# mainboard_mcu_v1_6.net
KiCad netlist of a schematic drawn in Altium Designer
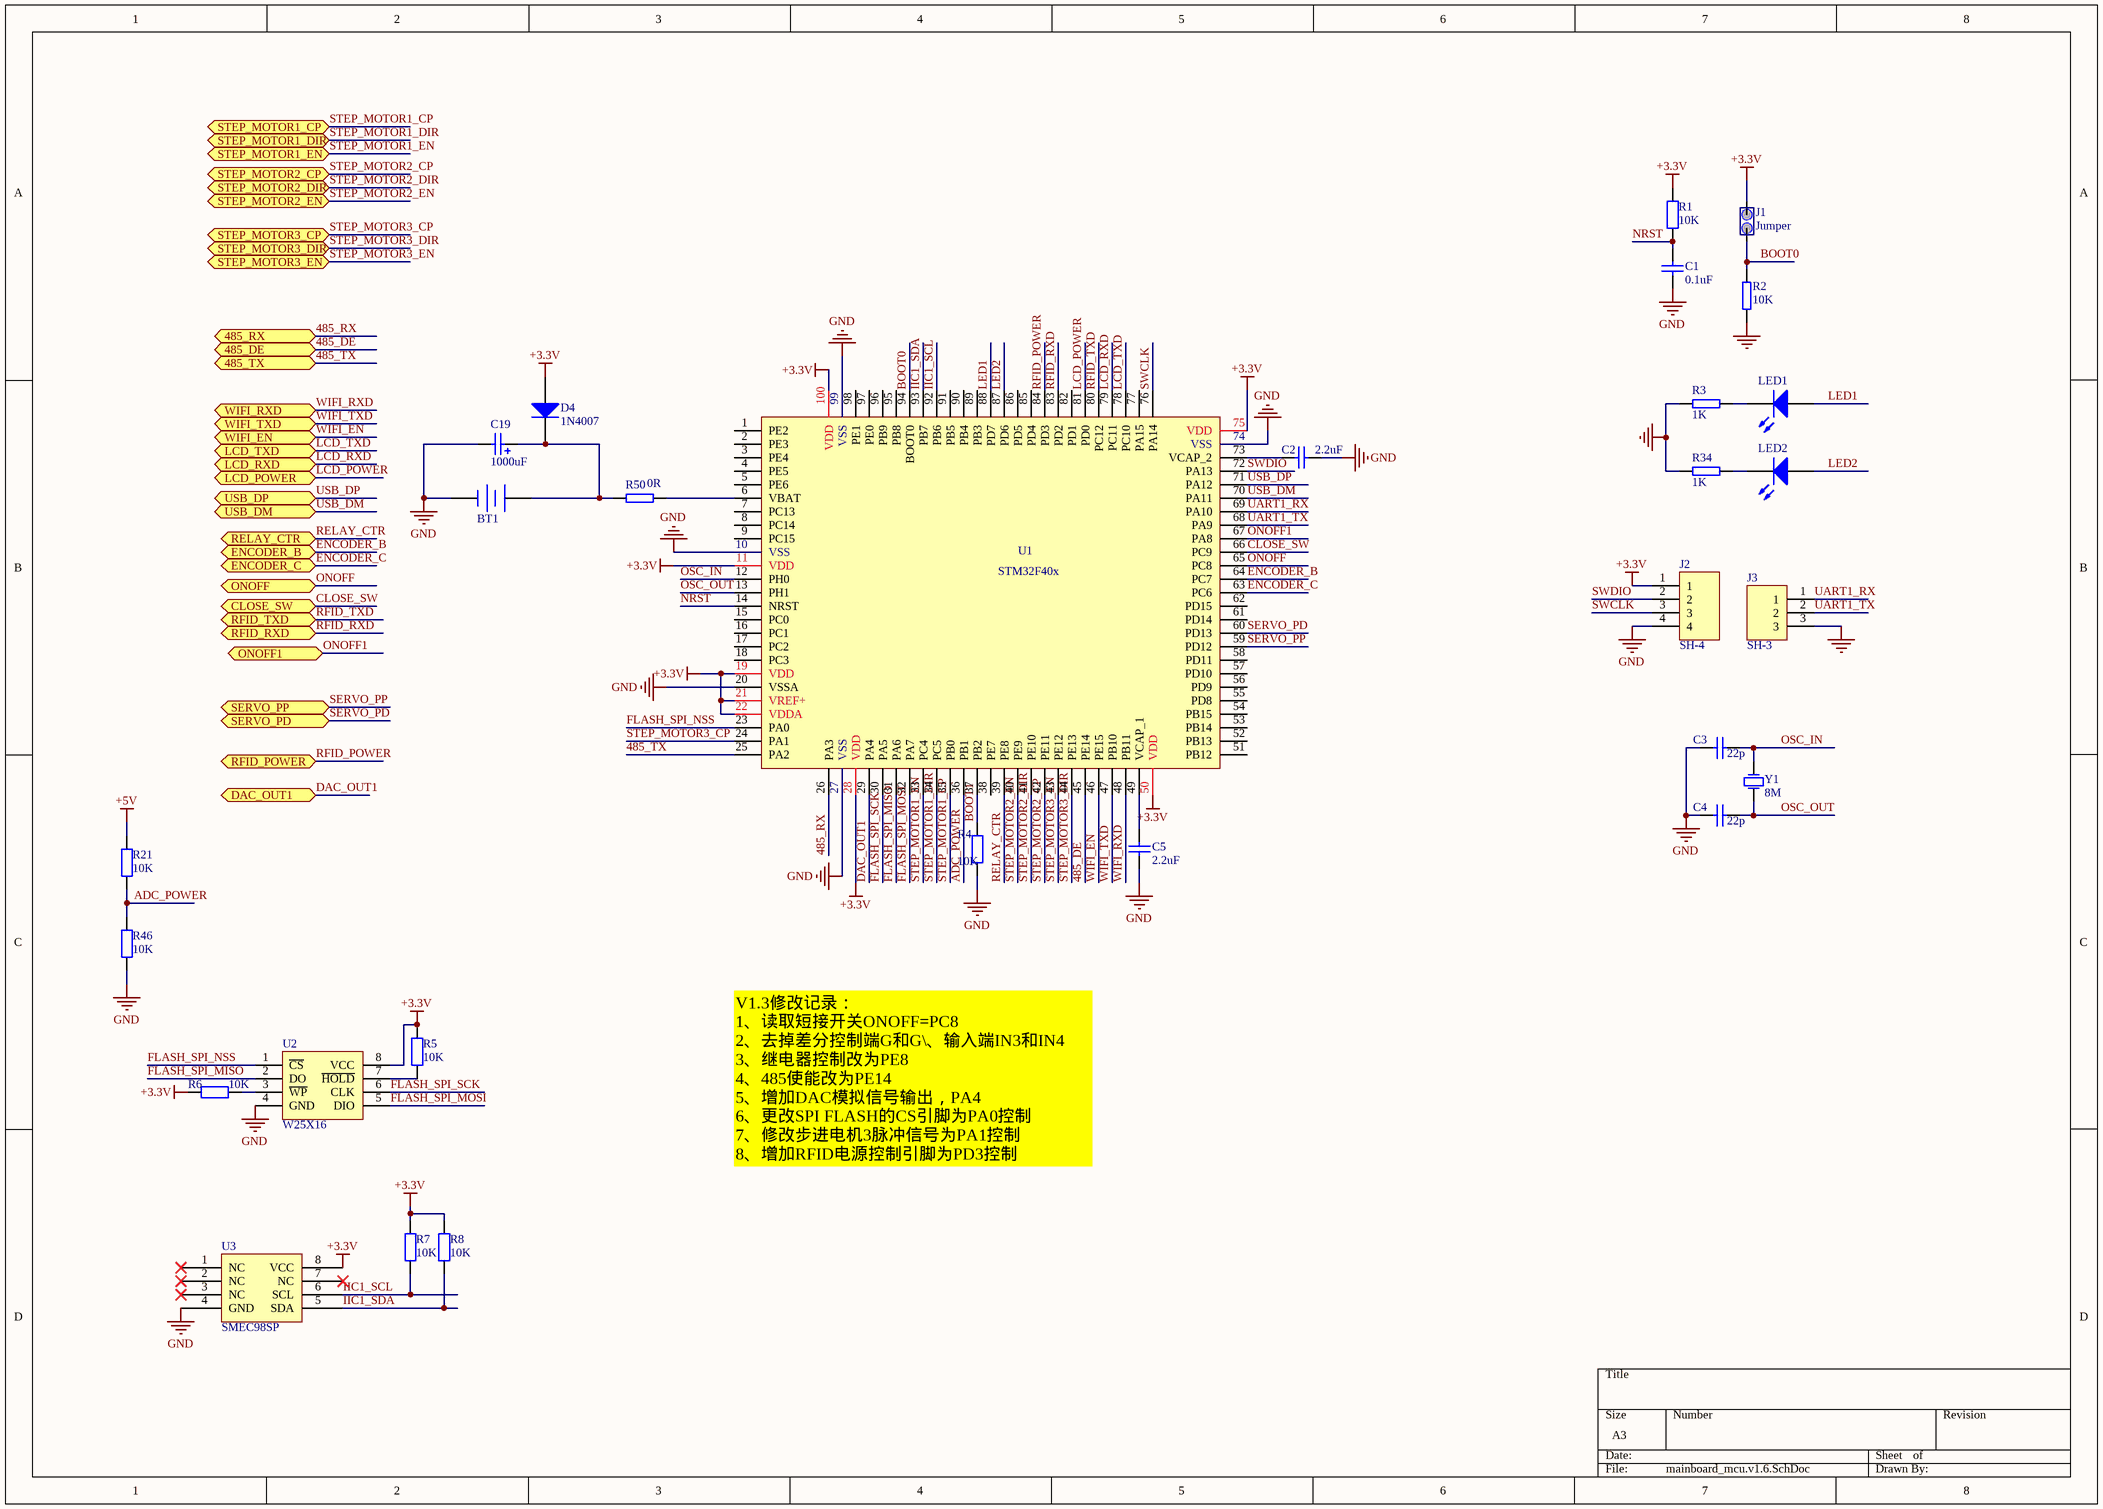
[diagram p0: mainboard_mcu.v1.6.SchDoc]

(export (version "E")
  (design (tool "Eeschema 10.0.6"))
  (components
    (comp (ref "BT1")
      (value "CR1220")
      (footprint "CR1220")
      (description "Multicell Battery")
      (fields (field (name "PUBLISHER") "Altium Limited"))
      (libsource (lib "Miscellaneous Devices") (part "Battery"))
    )
    (comp (ref "C1")
      (value "0.1uF")
      (footprint "0805")
      (description "Capacitor")
      (fields (field (name "PUBLISHER") "Altium Limited"))
      (libsource (lib "TIAN's Schlib") (part "Cap"))
    )
    (comp (ref "C2")
      (value "2.2uF")
      (footprint "0805")
      (description "Capacitor")
      (fields (field (name "PUBLISHER") "Altium Limited"))
      (libsource (lib "TIAN's Schlib") (part "Cap"))
    )
    (comp (ref "C3")
      (value "22p")
      (footprint "0805")
      (description "Capacitor")
      (fields (field (name "PUBLISHER") "Altium Limited"))
      (libsource (lib "TIAN's Schlib") (part "Cap"))
    )
    (comp (ref "C4")
      (value "22p")
      (footprint "0805")
      (description "Capacitor")
      (fields (field (name "PUBLISHER") "Altium Limited"))
      (libsource (lib "TIAN's Schlib") (part "Cap"))
    )
    (comp (ref "C5")
      (value "2.2uF")
      (footprint "0805")
      (description "Capacitor")
      (fields (field (name "PUBLISHER") "Altium Limited"))
      (libsource (lib "TIAN's Schlib") (part "Cap"))
    )
    (comp (ref "C19")
      (value "1000uF")
      (footprint "CAP_SMT_10X10")
      (description "Polarized Capacitor (Radial)")
      (fields (field (name "PUBLISHER") "Altium Limited"))
      (libsource (lib "Miscellaneous Devices") (part "Cap Pol1"))
    )
    (comp (ref "D4")
      (value "1N4007")
      (footprint "Diode_TP")
      (description "Default Diode")
      (fields (field (name "PUBLISHER") "Altium Limited"))
      (libsource (lib "Miscellaneous Devices") (part "Diode"))
    )
    (comp (ref "J1") (value "Jumper") (footprint "J254-2") (libsource (lib "Connector") (part "Jumper")))
    (comp (ref "J2") (value "SH-4") (footprint "J254-4") (libsource (lib "Connector") (part "SH-4")))
    (comp (ref "J3") (value "SH-3") (footprint "J2.54-3") (libsource (lib "Connector") (part "SH-3")))
    (comp (ref "LED1")
      (value "GREEN")
      (footprint "LED")
      (description "Typical RED, GREEN, YELLOW, AMBER GaAs LED")
      (fields (field (name "PUBLISHER") "Altium Limited"))
      (libsource (lib "Miscellaneous Devices") (part "LED2"))
    )
    (comp (ref "LED2")
      (value "GREEN")
      (footprint "LED")
      (description "Typical RED, GREEN, YELLOW, AMBER GaAs LED")
      (fields (field (name "PUBLISHER") "Altium Limited"))
      (libsource (lib "Miscellaneous Devices") (part "LED2"))
    )
    (comp (ref "R1")
      (value "10K")
      (footprint "0805")
      (description "Resistor")
      (fields (field (name "PUBLISHER") "Altium Limited"))
      (libsource (lib "TIAN's Schlib") (part "Res2"))
    )
    (comp (ref "R2")
      (value "10K")
      (footprint "0805")
      (description "电阻")
      (libsource (lib "Component") (part "RES"))
    )
    (comp (ref "R3")
      (value "1K")
      (footprint "0805")
      (description "电阻")
      (libsource (lib "Component") (part "RES"))
    )
    (comp (ref "R4")
      (value "10K")
      (footprint "0805")
      (description "Resistor")
      (fields (field (name "PUBLISHER") "Altium Limited"))
      (libsource (lib "") (part "Res2_1"))
    )
    (comp (ref "R5")
      (value "10K")
      (footprint "0805")
      (description "Resistor")
      (fields (field (name "PUBLISHER") "Altium Limited"))
      (libsource (lib "") (part "Res2_1"))
    )
    (comp (ref "R6")
      (value "10K")
      (footprint "0805")
      (description "Resistor")
      (fields (field (name "PUBLISHER") "Altium Limited"))
      (libsource (lib "") (part "Res2_2"))
    )
    (comp (ref "R7")
      (value "10K")
      (footprint "0805")
      (description "Resistor")
      (fields (field (name "PUBLISHER") "Altium Limited"))
      (libsource (lib "TIAN's Schlib") (part "Res2"))
    )
    (comp (ref "R8")
      (value "10K")
      (footprint "0805")
      (description "Resistor")
      (fields (field (name "PUBLISHER") "Altium Limited"))
      (libsource (lib "TIAN's Schlib") (part "Res2"))
    )
    (comp (ref "R21")
      (value "10K")
      (footprint "0805")
      (description "Resistor")
      (fields (field (name "PUBLISHER") "Altium Limited"))
      (libsource (lib "TIAN's Schlib") (part "Res2"))
    )
    (comp (ref "R34")
      (value "1K")
      (footprint "0805")
      (description "电阻")
      (libsource (lib "Component") (part "RES"))
    )
    (comp (ref "R46")
      (value "10K")
      (footprint "0805")
      (description "Resistor")
      (fields (field (name "PUBLISHER") "Altium Limited"))
      (libsource (lib "TIAN's Schlib") (part "Res2"))
    )
    (comp (ref "R50")
      (value "0R")
      (footprint "0805")
      (description "电阻")
      (libsource (lib "Component") (part "RES"))
    )
    (comp (ref "U1") (value "STM32F40x") (footprint "TQFP100") (libsource (lib "Chip") (part "STM32F40x")))
    (comp (ref "U2") (value "W25X16") (footprint "SOP8") (libsource (lib "Chip") (part "W25X16")))
    (comp (ref "U3") (value "SMEC98SP") (footprint "SO-8") (libsource (lib "Chip") (part "SMEC98SP")))
    (comp (ref "Y1")
      (value "8M")
      (footprint "XTAL")
      (description "Crystal Oscillator")
      (fields (field (name "PUBLISHER") "Altium Limited"))
      (libsource (lib "TIAN's Schlib") (part "X-32.768"))
    )
  )
  (nets
    (net (code "1") (name "+3.3V") (class "Default")
      (node (ref "D4") (pin "1") (pinfunction "A_1") (pintype "passive"))
      (node (ref "J1") (pin "2") (pinfunction "2_2") (pintype "passive"))
      (node (ref "J2") (pin "1") (pinfunction "1_1") (pintype "passive"))
      (node (ref "R1") (pin "2") (pinfunction "2_2") (pintype "passive"))
      (node (ref "R5") (pin "1") (pinfunction "1_1") (pintype "passive"))
      (node (ref "R6") (pin "2") (pinfunction "2_2") (pintype "passive"))
      (node (ref "R7") (pin "2") (pinfunction "2_2") (pintype "passive"))
      (node (ref "R8") (pin "2") (pinfunction "2_2") (pintype "passive"))
      (node (ref "U1") (pin "100") (pinfunction "VDD_100") (pintype "passive"))
      (node (ref "U1") (pin "11") (pinfunction "VDD_11") (pintype "passive"))
      (node (ref "U1") (pin "19") (pinfunction "VDD_19") (pintype "passive"))
      (node (ref "U1") (pin "21") (pinfunction "VREF+_21") (pintype "passive"))
      (node (ref "U1") (pin "22") (pinfunction "VDDA_22") (pintype "passive"))
      (node (ref "U1") (pin "28") (pinfunction "VDD_28") (pintype "passive"))
      (node (ref "U1") (pin "50") (pinfunction "VDD_50") (pintype "passive"))
      (node (ref "U1") (pin "75") (pinfunction "VDD_75") (pintype "passive"))
      (node (ref "U2") (pin "8") (pinfunction "VCC_8") (pintype "passive"))
      (node (ref "U3") (pin "8") (pinfunction "VCC_8") (pintype "passive"))
    )
    (net (code "2") (name "+5V") (class "Default")
      (node (ref "R21") (pin "2") (pinfunction "2_2") (pintype "passive"))
    )
    (net (code "3") (name "/485_DE") (class "Default")
      (node (ref "U1") (pin "45") (pinfunction "PE14_45") (pintype "passive"))
    )
    (net (code "4") (name "/485_RX") (class "Default")
      (node (ref "U1") (pin "26") (pinfunction "PA3_26") (pintype "passive"))
    )
    (net (code "5") (name "/485_TX") (class "Default")
      (node (ref "U1") (pin "25") (pinfunction "PA2_25") (pintype "passive"))
    )
    (net (code "6") (name "/ADC_POWER") (class "Default")
      (node (ref "R21") (pin "1") (pinfunction "1_1") (pintype "passive"))
      (node (ref "R46") (pin "2") (pinfunction "2_2") (pintype "passive"))
      (node (ref "U1") (pin "36") (pinfunction "PB1_36") (pintype "passive"))
    )
    (net (code "7") (name "/BOOT0") (class "Default")
      (node (ref "J1") (pin "1") (pinfunction "1_1") (pintype "passive"))
      (node (ref "R2") (pin "1") (pinfunction "1_1") (pintype "passive"))
      (node (ref "U1") (pin "94") (pinfunction "BOOT0_94") (pintype "passive"))
    )
    (net (code "8") (name "/BOOT1") (class "Default")
      (node (ref "R4") (pin "1") (pinfunction "1_1") (pintype "passive"))
      (node (ref "U1") (pin "37") (pinfunction "PB2_37") (pintype "passive"))
    )
    (net (code "9") (name "/CLOSE_SW") (class "Default")
      (node (ref "U1") (pin "66") (pinfunction "PC9_66") (pintype "passive"))
    )
    (net (code "10") (name "/DAC_OUT1") (class "Default")
      (node (ref "U1") (pin "29") (pinfunction "PA4_29") (pintype "passive"))
    )
    (net (code "11") (name "/ENCODER_B") (class "Default")
      (node (ref "U1") (pin "64") (pinfunction "PC7_64") (pintype "passive"))
    )
    (net (code "12") (name "/ENCODER_C") (class "Default")
      (node (ref "U1") (pin "63") (pinfunction "PC6_63") (pintype "passive"))
    )
    (net (code "13") (name "/FLASH_SPI_MISO") (class "Default")
      (node (ref "U1") (pin "31") (pinfunction "PA6_31") (pintype "passive"))
      (node (ref "U2") (pin "2") (pinfunction "DO_2") (pintype "passive"))
    )
    (net (code "14") (name "/FLASH_SPI_MOSI") (class "Default")
      (node (ref "U1") (pin "32") (pinfunction "PA7_32") (pintype "passive"))
      (node (ref "U2") (pin "5") (pinfunction "DIO_5") (pintype "passive"))
    )
    (net (code "15") (name "/FLASH_SPI_NSS") (class "Default")
      (node (ref "U1") (pin "23") (pinfunction "PA0_23") (pintype "passive"))
      (node (ref "U2") (pin "1") (pinfunction "~{CS}_1") (pintype "passive"))
    )
    (net (code "16") (name "/FLASH_SPI_SCK") (class "Default")
      (node (ref "U1") (pin "30") (pinfunction "PA5_30") (pintype "passive"))
      (node (ref "U2") (pin "6") (pinfunction "CLK_6") (pintype "passive"))
    )
    (net (code "17") (name "/IIC1_SCL") (class "Default")
      (node (ref "R7") (pin "1") (pinfunction "1_1") (pintype "passive"))
      (node (ref "U1") (pin "92") (pinfunction "PB6_92") (pintype "passive"))
      (node (ref "U3") (pin "6") (pinfunction "SCL_6") (pintype "passive"))
    )
    (net (code "18") (name "/IIC1_SDA") (class "Default")
      (node (ref "R8") (pin "1") (pinfunction "1_1") (pintype "passive"))
      (node (ref "U1") (pin "93") (pinfunction "PB7_93") (pintype "passive"))
      (node (ref "U3") (pin "5") (pinfunction "SDA_5") (pintype "passive"))
    )
    (net (code "19") (name "/LCD_POWER") (class "Default")
      (node (ref "U1") (pin "81") (pinfunction "PD0_81") (pintype "passive"))
    )
    (net (code "20") (name "/LCD_RXD") (class "Default")
      (node (ref "U1") (pin "79") (pinfunction "PC11_79") (pintype "passive"))
    )
    (net (code "21") (name "/LCD_TXD") (class "Default")
      (node (ref "U1") (pin "78") (pinfunction "PC10_78") (pintype "passive"))
    )
    (net (code "22") (name "/LED1") (class "Default")
      (node (ref "LED1") (pin "1") (pinfunction "A_1") (pintype "passive"))
      (node (ref "U1") (pin "88") (pinfunction "PD7_88") (pintype "passive"))
    )
    (net (code "23") (name "/LED2") (class "Default")
      (node (ref "LED2") (pin "1") (pinfunction "A_1") (pintype "passive"))
      (node (ref "U1") (pin "87") (pinfunction "PD6_87") (pintype "passive"))
    )
    (net (code "24") (name "/NRST") (class "Default")
      (node (ref "C1") (pin "2") (pinfunction "2_2") (pintype "passive"))
      (node (ref "R1") (pin "1") (pinfunction "1_1") (pintype "passive"))
      (node (ref "U1") (pin "14") (pinfunction "NRST_14") (pintype "passive"))
    )
    (net (code "25") (name "/ONOFF") (class "Default")
      (node (ref "U1") (pin "65") (pinfunction "PC8_65") (pintype "passive"))
    )
    (net (code "26") (name "/ONOFF1") (class "Default")
      (node (ref "U1") (pin "67") (pinfunction "PA8_67") (pintype "passive"))
    )
    (net (code "27") (name "/OSC_IN") (class "Default")
      (node (ref "C3") (pin "1") (pinfunction "1_1") (pintype "passive"))
      (node (ref "U1") (pin "12") (pinfunction "PH0_12") (pintype "passive"))
      (node (ref "Y1") (pin "2") (pinfunction "OSC2_2") (pintype "passive"))
    )
    (net (code "28") (name "/OSC_OUT") (class "Default")
      (node (ref "C4") (pin "1") (pinfunction "1_1") (pintype "passive"))
      (node (ref "U1") (pin "13") (pinfunction "PH1_13") (pintype "passive"))
      (node (ref "Y1") (pin "1") (pinfunction "OSC1_1") (pintype "passive"))
    )
    (net (code "29") (name "/RELAY_CTR") (class "Default")
      (node (ref "U1") (pin "39") (pinfunction "PE8_39") (pintype "passive"))
    )
    (net (code "30") (name "/RFID_POWER") (class "Default")
      (node (ref "U1") (pin "84") (pinfunction "PD3_84") (pintype "passive"))
    )
    (net (code "31") (name "/RFID_RXD") (class "Default")
      (node (ref "U1") (pin "83") (pinfunction "PD2_83") (pintype "passive"))
    )
    (net (code "32") (name "/RFID_TXD") (class "Default")
      (node (ref "U1") (pin "80") (pinfunction "PC12_80") (pintype "passive"))
    )
    (net (code "33") (name "/SERVO_PD") (class "Default")
      (node (ref "U1") (pin "60") (pinfunction "PD13_60") (pintype "passive"))
    )
    (net (code "34") (name "/SERVO_PP") (class "Default")
      (node (ref "U1") (pin "59") (pinfunction "PD12_59") (pintype "passive"))
    )
    (net (code "35") (name "/STEP_MOTOR1_CP") (class "Default")
      (node (ref "U1") (pin "35") (pinfunction "PB0_35") (pintype "passive"))
    )
    (net (code "36") (name "/STEP_MOTOR1_DIR") (class "Default")
      (node (ref "U1") (pin "34") (pinfunction "PC5_34") (pintype "passive"))
    )
    (net (code "37") (name "/STEP_MOTOR1_EN") (class "Default")
      (node (ref "U1") (pin "33") (pinfunction "PC4_33") (pintype "passive"))
    )
    (net (code "38") (name "/STEP_MOTOR2_CP") (class "Default")
      (node (ref "U1") (pin "42") (pinfunction "PE11_42") (pintype "passive"))
    )
    (net (code "39") (name "/STEP_MOTOR2_DIR") (class "Default")
      (node (ref "U1") (pin "41") (pinfunction "PE10_41") (pintype "passive"))
    )
    (net (code "40") (name "/STEP_MOTOR2_EN") (class "Default")
      (node (ref "U1") (pin "40") (pinfunction "PE9_40") (pintype "passive"))
    )
    (net (code "41") (name "/STEP_MOTOR3_CP") (class "Default")
      (node (ref "U1") (pin "24") (pinfunction "PA1_24") (pintype "passive"))
    )
    (net (code "42") (name "/STEP_MOTOR3_DIR") (class "Default")
      (node (ref "U1") (pin "44") (pinfunction "PE13_44") (pintype "passive"))
    )
    (net (code "43") (name "/STEP_MOTOR3_EN") (class "Default")
      (node (ref "U1") (pin "43") (pinfunction "PE12_43") (pintype "passive"))
    )
    (net (code "44") (name "/SWCLK") (class "Default")
      (node (ref "J2") (pin "3") (pinfunction "3_3") (pintype "passive"))
      (node (ref "U1") (pin "76") (pinfunction "PA14_76") (pintype "passive"))
    )
    (net (code "45") (name "/SWDIO") (class "Default")
      (node (ref "J2") (pin "2") (pinfunction "2_2") (pintype "passive"))
      (node (ref "U1") (pin "72") (pinfunction "PA13_72") (pintype "passive"))
    )
    (net (code "46") (name "/UART1_RX") (class "Default")
      (node (ref "J3") (pin "1") (pinfunction "1_1") (pintype "passive"))
      (node (ref "U1") (pin "69") (pinfunction "PA10_69") (pintype "passive"))
    )
    (net (code "47") (name "/UART1_TX") (class "Default")
      (node (ref "J3") (pin "2") (pinfunction "2_2") (pintype "passive"))
      (node (ref "U1") (pin "68") (pinfunction "PA9_68") (pintype "passive"))
    )
    (net (code "48") (name "/USB_DM") (class "Default")
      (node (ref "U1") (pin "70") (pinfunction "PA11_70") (pintype "passive"))
    )
    (net (code "49") (name "/USB_DP") (class "Default")
      (node (ref "U1") (pin "71") (pinfunction "PA12_71") (pintype "passive"))
    )
    (net (code "50") (name "/WIFI_EN") (class "Default")
      (node (ref "U1") (pin "46") (pinfunction "PE15_46") (pintype "passive"))
    )
    (net (code "51") (name "/WIFI_RXD") (class "Default")
      (node (ref "U1") (pin "48") (pinfunction "PB11_48") (pintype "passive"))
    )
    (net (code "52") (name "/WIFI_TXD") (class "Default")
      (node (ref "U1") (pin "47") (pinfunction "PB10_47") (pintype "passive"))
    )
    (net (code "53") (name "GND") (class "Default")
      (node (ref "BT1") (pin "2") (pinfunction "-_2") (pintype "passive"))
      (node (ref "C1") (pin "1") (pinfunction "1_1") (pintype "passive"))
      (node (ref "C19") (pin "2") (pinfunction "2_2") (pintype "passive"))
      (node (ref "C2") (pin "1") (pinfunction "1_1") (pintype "passive"))
      (node (ref "C3") (pin "2") (pinfunction "2_2") (pintype "passive"))
      (node (ref "C4") (pin "2") (pinfunction "2_2") (pintype "passive"))
      (node (ref "C5") (pin "2") (pinfunction "2_2") (pintype "passive"))
      (node (ref "J2") (pin "4") (pinfunction "4_4") (pintype "passive"))
      (node (ref "J3") (pin "3") (pinfunction "3_3") (pintype "passive"))
      (node (ref "R2") (pin "2") (pinfunction "2_2") (pintype "passive"))
      (node (ref "R3") (pin "2") (pinfunction "2_2") (pintype "passive"))
      (node (ref "R34") (pin "2") (pinfunction "2_2") (pintype "passive"))
      (node (ref "R4") (pin "2") (pinfunction "2_2") (pintype "passive"))
      (node (ref "R46") (pin "1") (pinfunction "1_1") (pintype "passive"))
      (node (ref "U1") (pin "10") (pinfunction "VSS_10") (pintype "passive"))
      (node (ref "U1") (pin "20") (pinfunction "VSSA_20") (pintype "passive"))
      (node (ref "U1") (pin "27") (pinfunction "VSS_27") (pintype "passive"))
      (node (ref "U1") (pin "74") (pinfunction "VSS_74") (pintype "passive"))
      (node (ref "U1") (pin "99") (pinfunction "VSS_99") (pintype "passive"))
      (node (ref "U2") (pin "4") (pinfunction "GND_4") (pintype "passive"))
      (node (ref "U3") (pin "4") (pinfunction "GND_4") (pintype "passive"))
    )
    (net (code "54") (name "Net-(BT1-+)") (class "Default")
      (node (ref "BT1") (pin "1") (pinfunction "+_1") (pintype "passive"))
      (node (ref "C19") (pin "1") (pinfunction "1_1") (pintype "passive"))
      (node (ref "D4") (pin "2") (pinfunction "K_2") (pintype "passive"))
      (node (ref "R50") (pin "1") (pinfunction "1_1") (pintype "passive"))
    )
    (net (code "55") (name "Net-(LED1-K)") (class "Default")
      (node (ref "LED1") (pin "2") (pinfunction "K_2") (pintype "passive"))
      (node (ref "R3") (pin "1") (pinfunction "1_1") (pintype "passive"))
    )
    (net (code "56") (name "Net-(LED2-K)") (class "Default")
      (node (ref "LED2") (pin "2") (pinfunction "K_2") (pintype "passive"))
      (node (ref "R34") (pin "1") (pinfunction "1_1") (pintype "passive"))
    )
    (net (code "57") (name "Net-(U1-VBAT)") (class "Default")
      (node (ref "R50") (pin "2") (pinfunction "2_2") (pintype "passive"))
      (node (ref "U1") (pin "6") (pinfunction "VBAT_6") (pintype "passive"))
    )
    (net (code "58") (name "Net-(U1-VCAP_1)") (class "Default")
      (node (ref "C5") (pin "1") (pinfunction "1_1") (pintype "passive"))
      (node (ref "U1") (pin "49") (pinfunction "VCAP_1_49") (pintype "passive"))
    )
    (net (code "59") (name "Net-(U1-VCAP_2)") (class "Default")
      (node (ref "C2") (pin "2") (pinfunction "2_2") (pintype "passive"))
      (node (ref "U1") (pin "73") (pinfunction "VCAP_2_73") (pintype "passive"))
    )
    (net (code "60") (name "Net-(U2-~{HOLD})") (class "Default")
      (node (ref "R5") (pin "2") (pinfunction "2_2") (pintype "passive"))
      (node (ref "U2") (pin "7") (pinfunction "~{HOLD}_7") (pintype "passive"))
    )
    (net (code "61") (name "Net-(U2-~{WP})") (class "Default")
      (node (ref "R6") (pin "1") (pinfunction "1_1") (pintype "passive"))
      (node (ref "U2") (pin "3") (pinfunction "~{WP}_3") (pintype "passive"))
    )
    (net (code "62") (name "unconnected-(U1-PA15-Pad77)") (class "Default")
      (node (ref "U1") (pin "77") (pinfunction "PA15_77") (pintype "passive"))
    )
    (net (code "63") (name "unconnected-(U1-PB3-Pad89)") (class "Default")
      (node (ref "U1") (pin "89") (pinfunction "PB3_89") (pintype "passive"))
    )
    (net (code "64") (name "unconnected-(U1-PB4-Pad90)") (class "Default")
      (node (ref "U1") (pin "90") (pinfunction "PB4_90") (pintype "passive"))
    )
    (net (code "65") (name "unconnected-(U1-PB5-Pad91)") (class "Default")
      (node (ref "U1") (pin "91") (pinfunction "PB5_91") (pintype "passive"))
    )
    (net (code "66") (name "unconnected-(U1-PB8-Pad95)") (class "Default")
      (node (ref "U1") (pin "95") (pinfunction "PB8_95") (pintype "passive"))
    )
    (net (code "67") (name "unconnected-(U1-PB9-Pad96)") (class "Default")
      (node (ref "U1") (pin "96") (pinfunction "PB9_96") (pintype "passive"))
    )
    (net (code "68") (name "unconnected-(U1-PB12-Pad51)") (class "Default")
      (node (ref "U1") (pin "51") (pinfunction "PB12_51") (pintype "passive"))
    )
    (net (code "69") (name "unconnected-(U1-PB13-Pad52)") (class "Default")
      (node (ref "U1") (pin "52") (pinfunction "PB13_52") (pintype "passive"))
    )
    (net (code "70") (name "unconnected-(U1-PB14-Pad53)") (class "Default")
      (node (ref "U1") (pin "53") (pinfunction "PB14_53") (pintype "passive"))
    )
    (net (code "71") (name "unconnected-(U1-PB15-Pad54)") (class "Default")
      (node (ref "U1") (pin "54") (pinfunction "PB15_54") (pintype "passive"))
    )
    (net (code "72") (name "unconnected-(U1-PC0-Pad15)") (class "Default")
      (node (ref "U1") (pin "15") (pinfunction "PC0_15") (pintype "passive"))
    )
    (net (code "73") (name "unconnected-(U1-PC1-Pad16)") (class "Default")
      (node (ref "U1") (pin "16") (pinfunction "PC1_16") (pintype "passive"))
    )
    (net (code "74") (name "unconnected-(U1-PC2-Pad17)") (class "Default")
      (node (ref "U1") (pin "17") (pinfunction "PC2_17") (pintype "passive"))
    )
    (net (code "75") (name "unconnected-(U1-PC3-Pad18)") (class "Default")
      (node (ref "U1") (pin "18") (pinfunction "PC3_18") (pintype "passive"))
    )
    (net (code "76") (name "unconnected-(U1-PC13-Pad7)") (class "Default")
      (node (ref "U1") (pin "7") (pinfunction "PC13_7") (pintype "passive"))
    )
    (net (code "77") (name "unconnected-(U1-PC14-Pad8)") (class "Default")
      (node (ref "U1") (pin "8") (pinfunction "PC14_8") (pintype "passive"))
    )
    (net (code "78") (name "unconnected-(U1-PC15-Pad9)") (class "Default")
      (node (ref "U1") (pin "9") (pinfunction "PC15_9") (pintype "passive"))
    )
    (net (code "79") (name "unconnected-(U1-PD1-Pad82)") (class "Default")
      (node (ref "U1") (pin "82") (pinfunction "PD1_82") (pintype "passive"))
    )
    (net (code "80") (name "unconnected-(U1-PD4-Pad85)") (class "Default")
      (node (ref "U1") (pin "85") (pinfunction "PD4_85") (pintype "passive"))
    )
    (net (code "81") (name "unconnected-(U1-PD5-Pad86)") (class "Default")
      (node (ref "U1") (pin "86") (pinfunction "PD5_86") (pintype "passive"))
    )
    (net (code "82") (name "unconnected-(U1-PD8-Pad55)") (class "Default")
      (node (ref "U1") (pin "55") (pinfunction "PD8_55") (pintype "passive"))
    )
    (net (code "83") (name "unconnected-(U1-PD9-Pad56)") (class "Default")
      (node (ref "U1") (pin "56") (pinfunction "PD9_56") (pintype "passive"))
    )
    (net (code "84") (name "unconnected-(U1-PD10-Pad57)") (class "Default")
      (node (ref "U1") (pin "57") (pinfunction "PD10_57") (pintype "passive"))
    )
    (net (code "85") (name "unconnected-(U1-PD11-Pad58)") (class "Default")
      (node (ref "U1") (pin "58") (pinfunction "PD11_58") (pintype "passive"))
    )
    (net (code "86") (name "unconnected-(U1-PD14-Pad61)") (class "Default")
      (node (ref "U1") (pin "61") (pinfunction "PD14_61") (pintype "passive"))
    )
    (net (code "87") (name "unconnected-(U1-PD15-Pad62)") (class "Default")
      (node (ref "U1") (pin "62") (pinfunction "PD15_62") (pintype "passive"))
    )
    (net (code "88") (name "unconnected-(U1-PE0-Pad97)") (class "Default")
      (node (ref "U1") (pin "97") (pinfunction "PE0_97") (pintype "passive"))
    )
    (net (code "89") (name "unconnected-(U1-PE1-Pad98)") (class "Default")
      (node (ref "U1") (pin "98") (pinfunction "PE1_98") (pintype "passive"))
    )
    (net (code "90") (name "unconnected-(U1-PE2-Pad1)") (class "Default")
      (node (ref "U1") (pin "1") (pinfunction "PE2_1") (pintype "passive"))
    )
    (net (code "91") (name "unconnected-(U1-PE3-Pad2)") (class "Default")
      (node (ref "U1") (pin "2") (pinfunction "PE3_2") (pintype "passive"))
    )
    (net (code "92") (name "unconnected-(U1-PE4-Pad3)") (class "Default")
      (node (ref "U1") (pin "3") (pinfunction "PE4_3") (pintype "passive"))
    )
    (net (code "93") (name "unconnected-(U1-PE5-Pad4)") (class "Default")
      (node (ref "U1") (pin "4") (pinfunction "PE5_4") (pintype "passive"))
    )
    (net (code "94") (name "unconnected-(U1-PE6-Pad5)") (class "Default")
      (node (ref "U1") (pin "5") (pinfunction "PE6_5") (pintype "passive"))
    )
    (net (code "95") (name "unconnected-(U1-PE7-Pad38)") (class "Default")
      (node (ref "U1") (pin "38") (pinfunction "PE7_38") (pintype "passive"))
    )
    (net (code "96") (name "unconnected-(U3-NC-Pad1)") (class "Default")
      (node (ref "U3") (pin "1") (pinfunction "NC_1") (pintype "passive+no_connect"))
    )
    (net (code "97") (name "unconnected-(U3-NC-Pad2)") (class "Default")
      (node (ref "U3") (pin "2") (pinfunction "NC_2") (pintype "passive+no_connect"))
    )
    (net (code "98") (name "unconnected-(U3-NC-Pad3)") (class "Default")
      (node (ref "U3") (pin "3") (pinfunction "NC_3") (pintype "passive+no_connect"))
    )
    (net (code "99") (name "unconnected-(U3-NC-Pad7)") (class "Default")
      (node (ref "U3") (pin "7") (pinfunction "NC_7") (pintype "passive+no_connect"))
    )
  )
)
